# moduloComunicacao2-portas_l_gicas.net
KiCad netlist of a schematic drawn in EAGLE
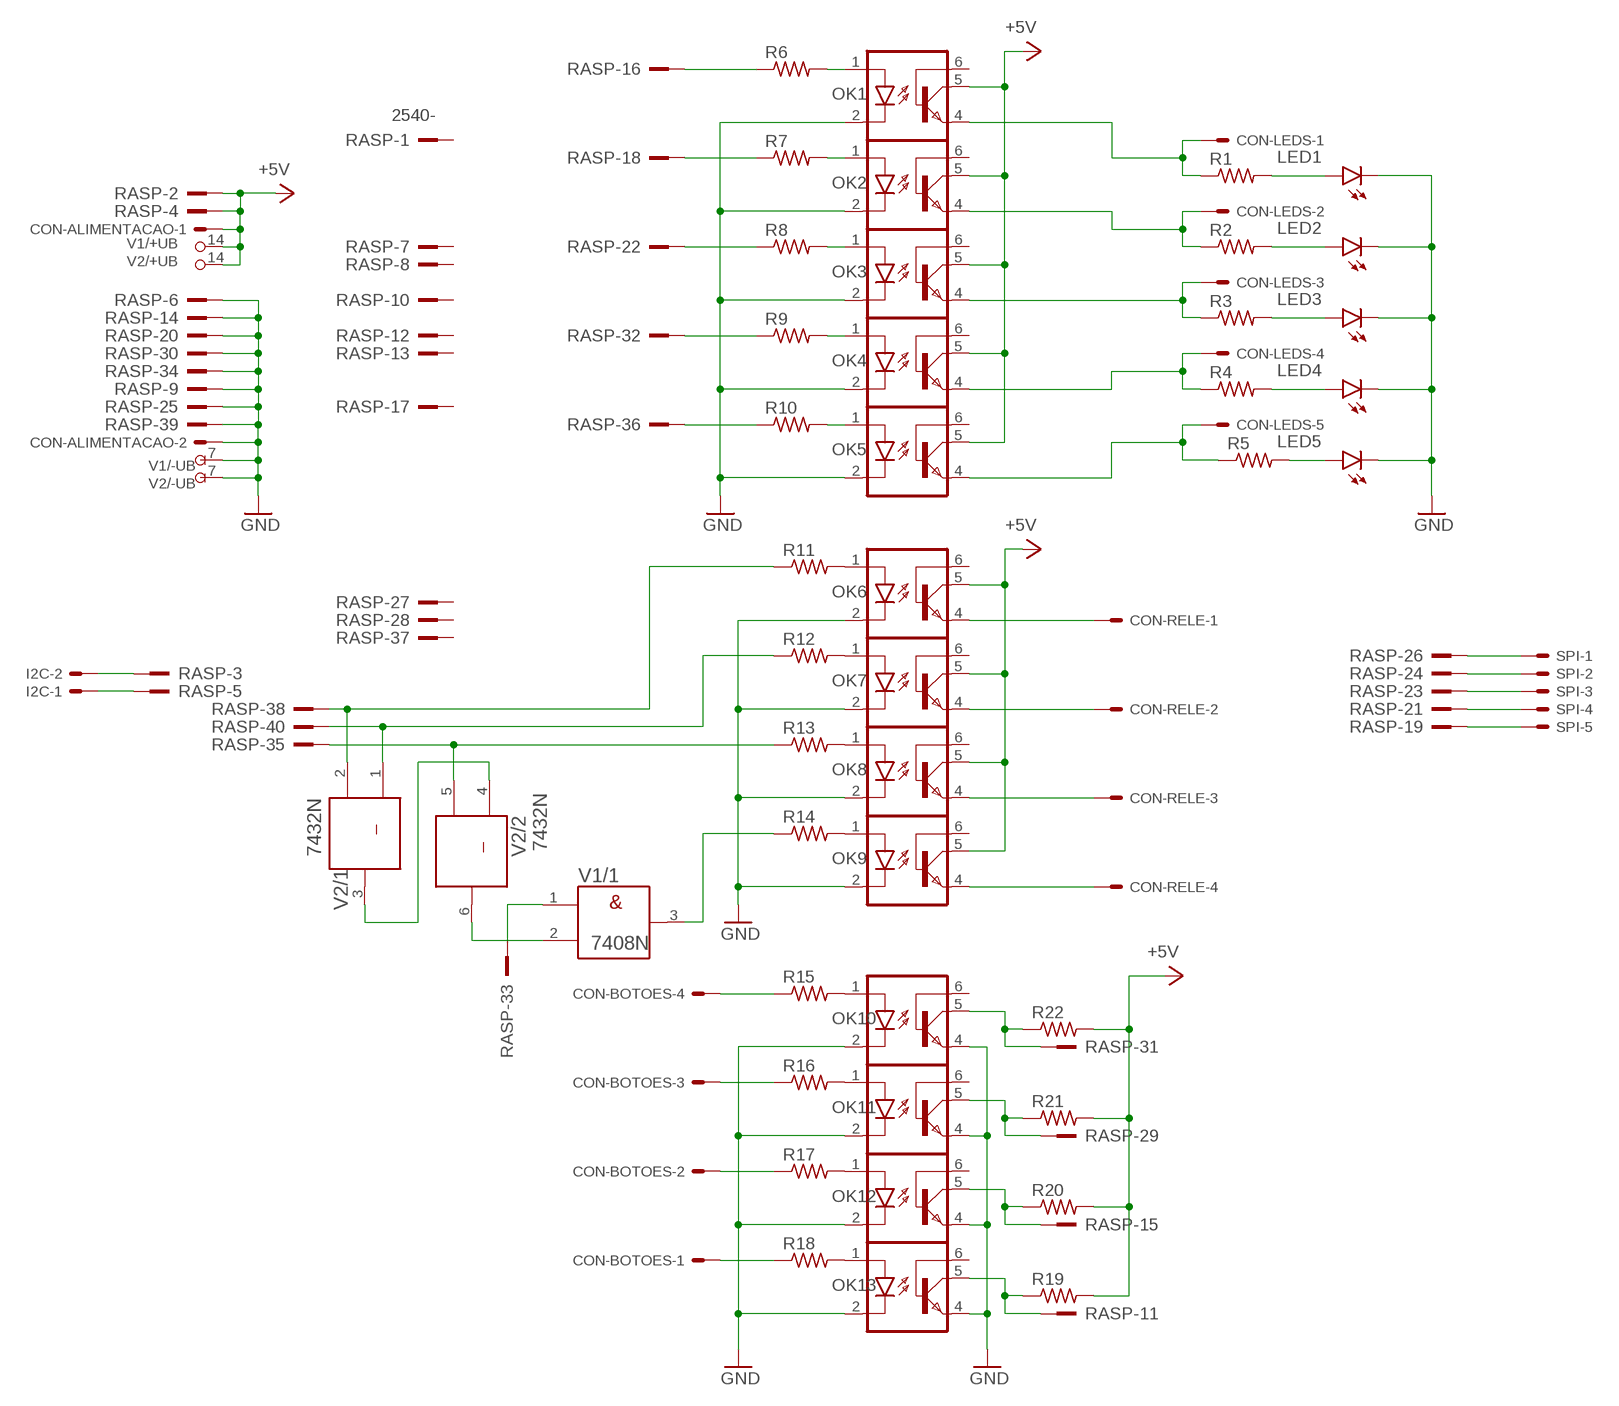
[diagram p0: schematic, sheet 1]

(export (version "E")
  (design (tool "Eeschema 10.0.6"))
  (components
    (comp (ref "CON-ALIMENTACAO")
      (value "22-23-2021")
      (footprint "eagle-import:22-23-2021")
      (fields (field (name "MF") "MOLEX"))
      (libsource (lib "eagle-import") (part "22-23-2021"))
    )
    (comp (ref "CON-BOTOES")
      (value "22-23-2041")
      (footprint "eagle-import:22-23-2041")
      (fields (field (name "MF") "MOLEX"))
      (libsource (lib "eagle-import") (part "22-23-2041"))
    )
    (comp (ref "CON-LEDS")
      (value "22-23-2051")
      (footprint "eagle-import:22-23-2051")
      (fields (field (name "MF") "MOLEX"))
      (libsource (lib "eagle-import") (part "22-23-2051"))
    )
    (comp (ref "CON-RELE")
      (value "22-23-2041")
      (footprint "eagle-import:22-23-2041")
      (fields (field (name "MF") "MOLEX"))
      (libsource (lib "eagle-import") (part "22-23-2041"))
    )
    (comp (ref "I2C")
      (value "22-23-2021")
      (footprint "eagle-import:22-23-2021")
      (fields (field (name "MF") "MOLEX"))
      (libsource (lib "eagle-import") (part "22-23-2021"))
    )
    (comp (ref "LED1")
      (value "LED5MM")
      (footprint "eagle-import:LED5MM")
      (libsource (lib "eagle-import") (part "LED5MM"))
    )
    (comp (ref "LED2")
      (value "LED5MM")
      (footprint "eagle-import:LED5MM")
      (libsource (lib "eagle-import") (part "LED5MM"))
    )
    (comp (ref "LED3")
      (value "LED5MM")
      (footprint "eagle-import:LED5MM")
      (libsource (lib "eagle-import") (part "LED5MM"))
    )
    (comp (ref "LED4")
      (value "LED5MM")
      (footprint "eagle-import:LED5MM")
      (libsource (lib "eagle-import") (part "LED5MM"))
    )
    (comp (ref "LED5")
      (value "LED5MM")
      (footprint "eagle-import:LED5MM")
      (libsource (lib "eagle-import") (part "LED5MM"))
    )
    (comp (ref "OK1")
      (value "4N25M")
      (footprint "eagle-import:DIL06")
      (fields (field (name "MPN") "4N25-M"))
      (libsource (lib "eagle-import") (part "4N?M25"))
    )
    (comp (ref "OK2")
      (value "4N25M")
      (footprint "eagle-import:DIL06")
      (fields (field (name "MPN") "4N25-M"))
      (libsource (lib "eagle-import") (part "4N?M25"))
    )
    (comp (ref "OK3")
      (value "4N25M")
      (footprint "eagle-import:DIL06")
      (fields (field (name "MPN") "4N25-M"))
      (libsource (lib "eagle-import") (part "4N?M25"))
    )
    (comp (ref "OK4")
      (value "4N25M")
      (footprint "eagle-import:DIL06")
      (fields (field (name "MPN") "4N25-M"))
      (libsource (lib "eagle-import") (part "4N?M25"))
    )
    (comp (ref "OK5")
      (value "4N25M")
      (footprint "eagle-import:DIL06")
      (fields (field (name "MPN") "4N25-M"))
      (libsource (lib "eagle-import") (part "4N?M25"))
    )
    (comp (ref "OK6")
      (value "4N25M")
      (footprint "eagle-import:DIL06")
      (fields (field (name "MPN") "4N25-M"))
      (libsource (lib "eagle-import") (part "4N?M25"))
    )
    (comp (ref "OK7")
      (value "4N25M")
      (footprint "eagle-import:DIL06")
      (fields (field (name "MPN") "4N25-M"))
      (libsource (lib "eagle-import") (part "4N?M25"))
    )
    (comp (ref "OK8")
      (value "4N25M")
      (footprint "eagle-import:DIL06")
      (fields (field (name "MPN") "4N25-M"))
      (libsource (lib "eagle-import") (part "4N?M25"))
    )
    (comp (ref "OK9")
      (value "4N25M")
      (footprint "eagle-import:DIL06")
      (fields (field (name "MPN") "4N25-M"))
      (libsource (lib "eagle-import") (part "4N?M25"))
    )
    (comp (ref "OK10")
      (value "4N25M")
      (footprint "eagle-import:DIL06")
      (fields (field (name "MPN") "4N25-M"))
      (libsource (lib "eagle-import") (part "4N?M25"))
    )
    (comp (ref "OK11")
      (value "4N25M")
      (footprint "eagle-import:DIL06")
      (fields (field (name "MPN") "4N25-M"))
      (libsource (lib "eagle-import") (part "4N?M25"))
    )
    (comp (ref "OK12")
      (value "4N25M")
      (footprint "eagle-import:DIL06")
      (fields (field (name "MPN") "4N25-M"))
      (libsource (lib "eagle-import") (part "4N?M25"))
    )
    (comp (ref "OK13")
      (value "4N25M")
      (footprint "eagle-import:DIL06")
      (fields (field (name "MPN") "4N25-M"))
      (libsource (lib "eagle-import") (part "4N?M25"))
    )
    (comp (ref "R1")
      (value "R-US_0207/12")
      (footprint "eagle-import:0207_12")
      (libsource (lib "eagle-import") (part "R-US_0207/12"))
    )
    (comp (ref "R2")
      (value "R-US_0207/12")
      (footprint "eagle-import:0207_12")
      (libsource (lib "eagle-import") (part "R-US_0207/12"))
    )
    (comp (ref "R3")
      (value "R-US_0207/12")
      (footprint "eagle-import:0207_12")
      (libsource (lib "eagle-import") (part "R-US_0207/12"))
    )
    (comp (ref "R4")
      (value "R-US_0207/12")
      (footprint "eagle-import:0207_12")
      (libsource (lib "eagle-import") (part "R-US_0207/12"))
    )
    (comp (ref "R5")
      (value "R-US_0207/12")
      (footprint "eagle-import:0207_12")
      (libsource (lib "eagle-import") (part "R-US_0207/12"))
    )
    (comp (ref "R6")
      (value "R-US_0204/7")
      (footprint "eagle-import:0204_7")
      (libsource (lib "eagle-import") (part "R-US_0204/7"))
    )
    (comp (ref "R7")
      (value "R-US_0204/7")
      (footprint "eagle-import:0204_7")
      (libsource (lib "eagle-import") (part "R-US_0204/7"))
    )
    (comp (ref "R8")
      (value "R-US_0204/7")
      (footprint "eagle-import:0204_7")
      (libsource (lib "eagle-import") (part "R-US_0204/7"))
    )
    (comp (ref "R9")
      (value "R-US_0204/7")
      (footprint "eagle-import:0204_7")
      (libsource (lib "eagle-import") (part "R-US_0204/7"))
    )
    (comp (ref "R10")
      (value "R-US_0204/7")
      (footprint "eagle-import:0204_7")
      (libsource (lib "eagle-import") (part "R-US_0204/7"))
    )
    (comp (ref "R11")
      (value "R-US_0204/7")
      (footprint "eagle-import:0204_7")
      (libsource (lib "eagle-import") (part "R-US_0204/7"))
    )
    (comp (ref "R12")
      (value "R-US_0204/7")
      (footprint "eagle-import:0204_7")
      (libsource (lib "eagle-import") (part "R-US_0204/7"))
    )
    (comp (ref "R13")
      (value "R-US_0204/7")
      (footprint "eagle-import:0204_7")
      (libsource (lib "eagle-import") (part "R-US_0204/7"))
    )
    (comp (ref "R14")
      (value "R-US_0204/7")
      (footprint "eagle-import:0204_7")
      (libsource (lib "eagle-import") (part "R-US_0204/7"))
    )
    (comp (ref "R15")
      (value "R-US_0207/10")
      (footprint "eagle-import:0207_10")
      (libsource (lib "eagle-import") (part "R-US_0207/10"))
    )
    (comp (ref "R16")
      (value "R-US_0207/10")
      (footprint "eagle-import:0207_10")
      (libsource (lib "eagle-import") (part "R-US_0207/10"))
    )
    (comp (ref "R17")
      (value "R-US_0207/10")
      (footprint "eagle-import:0207_10")
      (libsource (lib "eagle-import") (part "R-US_0207/10"))
    )
    (comp (ref "R18")
      (value "R-US_0207/10")
      (footprint "eagle-import:0207_10")
      (libsource (lib "eagle-import") (part "R-US_0207/10"))
    )
    (comp (ref "R19")
      (value "R-US_0204/7")
      (footprint "eagle-import:0204_7")
      (libsource (lib "eagle-import") (part "R-US_0204/7"))
    )
    (comp (ref "R20")
      (value "R-US_0204/7")
      (footprint "eagle-import:0204_7")
      (libsource (lib "eagle-import") (part "R-US_0204/7"))
    )
    (comp (ref "R21")
      (value "R-US_0204/7")
      (footprint "eagle-import:0204_7")
      (libsource (lib "eagle-import") (part "R-US_0204/7"))
    )
    (comp (ref "R22")
      (value "R-US_0204/7")
      (footprint "eagle-import:0204_7")
      (libsource (lib "eagle-import") (part "R-US_0204/7"))
    )
    (comp (ref "RASP")
      (value "2540-")
      (footprint "eagle-import:PAK100_2500-40")
      (libsource (lib "eagle-import") (part "2540-"))
    )
    (comp (ref "SPI")
      (value "22-23-2051")
      (footprint "eagle-import:22-23-2051")
      (fields (field (name "MF") "MOLEX"))
      (libsource (lib "eagle-import") (part "22-23-2051"))
    )
    (comp (ref "V1")
      (value "7408N")
      (footprint "eagle-import:DIL14")
      (libsource (lib "eagle-import") (part "7408N"))
    )
    (comp (ref "V2")
      (value "7432N")
      (footprint "eagle-import:DIL14")
      (libsource (lib "eagle-import") (part "7432N"))
    )
  )
  (nets
    (net (code "1") (name "+5V") (class "Default")
      (node (ref "CON-ALIMENTACAO") (pin "1") (pinfunction "S_1") (pintype "passive"))
      (node (ref "OK1") (pin "5") (pinfunction "COL_5") (pintype "passive"))
      (node (ref "OK2") (pin "5") (pinfunction "COL_5") (pintype "passive"))
      (node (ref "OK3") (pin "5") (pinfunction "COL_5") (pintype "passive"))
      (node (ref "OK4") (pin "5") (pinfunction "COL_5") (pintype "passive"))
      (node (ref "OK5") (pin "5") (pinfunction "COL_5") (pintype "passive"))
      (node (ref "OK6") (pin "5") (pinfunction "COL_5") (pintype "passive"))
      (node (ref "OK7") (pin "5") (pinfunction "COL_5") (pintype "passive"))
      (node (ref "OK8") (pin "5") (pinfunction "COL_5") (pintype "passive"))
      (node (ref "OK9") (pin "5") (pinfunction "COL_5") (pintype "passive"))
      (node (ref "R19") (pin "2") (pinfunction "2_2") (pintype "passive"))
      (node (ref "R20") (pin "2") (pinfunction "2_2") (pintype "passive"))
      (node (ref "R21") (pin "2") (pinfunction "2_2") (pintype "passive"))
      (node (ref "R22") (pin "2") (pinfunction "2_2") (pintype "passive"))
      (node (ref "RASP") (pin "2") (pinfunction "KL_2") (pintype "passive"))
      (node (ref "RASP") (pin "4") (pinfunction "KL_4") (pintype "passive"))
      (node (ref "V1") (pin "14") (pinfunction "+UB_14") (pintype "power_in"))
      (node (ref "V2") (pin "14") (pinfunction "+UB_14") (pintype "power_in"))
    )
    (net (code "2") (name "GND") (class "Default")
      (node (ref "CON-ALIMENTACAO") (pin "2") (pinfunction "S_2") (pintype "passive"))
      (node (ref "LED1") (pin "K") (pinfunction "C_K") (pintype "passive"))
      (node (ref "LED2") (pin "K") (pinfunction "C_K") (pintype "passive"))
      (node (ref "LED3") (pin "K") (pinfunction "C_K") (pintype "passive"))
      (node (ref "LED4") (pin "K") (pinfunction "C_K") (pintype "passive"))
      (node (ref "LED5") (pin "K") (pinfunction "C_K") (pintype "passive"))
      (node (ref "OK1") (pin "2") (pinfunction "C_2") (pintype "passive"))
      (node (ref "OK10") (pin "2") (pinfunction "C_2") (pintype "passive"))
      (node (ref "OK10") (pin "4") (pinfunction "EMI_4") (pintype "passive"))
      (node (ref "OK11") (pin "2") (pinfunction "C_2") (pintype "passive"))
      (node (ref "OK11") (pin "4") (pinfunction "EMI_4") (pintype "passive"))
      (node (ref "OK12") (pin "2") (pinfunction "C_2") (pintype "passive"))
      (node (ref "OK12") (pin "4") (pinfunction "EMI_4") (pintype "passive"))
      (node (ref "OK13") (pin "2") (pinfunction "C_2") (pintype "passive"))
      (node (ref "OK13") (pin "4") (pinfunction "EMI_4") (pintype "passive"))
      (node (ref "OK2") (pin "2") (pinfunction "C_2") (pintype "passive"))
      (node (ref "OK3") (pin "2") (pinfunction "C_2") (pintype "passive"))
      (node (ref "OK4") (pin "2") (pinfunction "C_2") (pintype "passive"))
      (node (ref "OK5") (pin "2") (pinfunction "C_2") (pintype "passive"))
      (node (ref "OK6") (pin "2") (pinfunction "C_2") (pintype "passive"))
      (node (ref "OK7") (pin "2") (pinfunction "C_2") (pintype "passive"))
      (node (ref "OK8") (pin "2") (pinfunction "C_2") (pintype "passive"))
      (node (ref "OK9") (pin "2") (pinfunction "C_2") (pintype "passive"))
      (node (ref "RASP") (pin "14") (pinfunction "KL_14") (pintype "passive"))
      (node (ref "RASP") (pin "20") (pinfunction "KL_20") (pintype "passive"))
      (node (ref "RASP") (pin "25") (pinfunction "KL_25") (pintype "passive"))
      (node (ref "RASP") (pin "30") (pinfunction "KL_30") (pintype "passive"))
      (node (ref "RASP") (pin "34") (pinfunction "KL_34") (pintype "passive"))
      (node (ref "RASP") (pin "39") (pinfunction "KL_39") (pintype "passive"))
      (node (ref "RASP") (pin "6") (pinfunction "KL_6") (pintype "passive"))
      (node (ref "RASP") (pin "9") (pinfunction "KL_9") (pintype "passive"))
      (node (ref "V1") (pin "7") (pinfunction "-UB_7") (pintype "power_in"))
      (node (ref "V2") (pin "7") (pinfunction "-UB_7") (pintype "power_in"))
    )
    (net (code "3") (name "Net-(CON-BOTOESA-S)") (class "Default")
      (node (ref "CON-BOTOES") (pin "1") (pinfunction "S_1") (pintype "passive"))
      (node (ref "R18") (pin "1") (pinfunction "1_1") (pintype "passive"))
    )
    (net (code "4") (name "Net-(CON-BOTOESB-S)") (class "Default")
      (node (ref "CON-BOTOES") (pin "2") (pinfunction "S_2") (pintype "passive"))
      (node (ref "R17") (pin "1") (pinfunction "1_1") (pintype "passive"))
    )
    (net (code "5") (name "Net-(CON-BOTOESC-S)") (class "Default")
      (node (ref "CON-BOTOES") (pin "3") (pinfunction "S_3") (pintype "passive"))
      (node (ref "R16") (pin "1") (pinfunction "1_1") (pintype "passive"))
    )
    (net (code "6") (name "Net-(CON-BOTOESD-S)") (class "Default")
      (node (ref "CON-BOTOES") (pin "4") (pinfunction "S_4") (pintype "passive"))
      (node (ref "R15") (pin "1") (pinfunction "1_1") (pintype "passive"))
    )
    (net (code "7") (name "Net-(CON-LEDSA-S)") (class "Default")
      (node (ref "CON-LEDS") (pin "1") (pinfunction "S_1") (pintype "passive"))
      (node (ref "OK1") (pin "4") (pinfunction "EMI_4") (pintype "passive"))
      (node (ref "R1") (pin "1") (pinfunction "1_1") (pintype "passive"))
    )
    (net (code "8") (name "Net-(CON-LEDSB-S)") (class "Default")
      (node (ref "CON-LEDS") (pin "2") (pinfunction "S_2") (pintype "passive"))
      (node (ref "OK2") (pin "4") (pinfunction "EMI_4") (pintype "passive"))
      (node (ref "R2") (pin "1") (pinfunction "1_1") (pintype "passive"))
    )
    (net (code "9") (name "Net-(CON-LEDSC-S)") (class "Default")
      (node (ref "CON-LEDS") (pin "3") (pinfunction "S_3") (pintype "passive"))
      (node (ref "OK3") (pin "4") (pinfunction "EMI_4") (pintype "passive"))
      (node (ref "R3") (pin "1") (pinfunction "1_1") (pintype "passive"))
    )
    (net (code "10") (name "Net-(CON-LEDSD-S)") (class "Default")
      (node (ref "CON-LEDS") (pin "4") (pinfunction "S_4") (pintype "passive"))
      (node (ref "OK4") (pin "4") (pinfunction "EMI_4") (pintype "passive"))
      (node (ref "R4") (pin "1") (pinfunction "1_1") (pintype "passive"))
    )
    (net (code "11") (name "Net-(CON-LEDSE-S)") (class "Default")
      (node (ref "CON-LEDS") (pin "5") (pinfunction "S_5") (pintype "passive"))
      (node (ref "OK5") (pin "4") (pinfunction "EMI_4") (pintype "passive"))
      (node (ref "R5") (pin "1") (pinfunction "1_1") (pintype "passive"))
    )
    (net (code "12") (name "Net-(CON-RELEA-S)") (class "Default")
      (node (ref "CON-RELE") (pin "1") (pinfunction "S_1") (pintype "passive"))
      (node (ref "OK6") (pin "4") (pinfunction "EMI_4") (pintype "passive"))
    )
    (net (code "13") (name "Net-(CON-RELEB-S)") (class "Default")
      (node (ref "CON-RELE") (pin "2") (pinfunction "S_2") (pintype "passive"))
      (node (ref "OK7") (pin "4") (pinfunction "EMI_4") (pintype "passive"))
    )
    (net (code "14") (name "Net-(CON-RELEC-S)") (class "Default")
      (node (ref "CON-RELE") (pin "3") (pinfunction "S_3") (pintype "passive"))
      (node (ref "OK8") (pin "4") (pinfunction "EMI_4") (pintype "passive"))
    )
    (net (code "15") (name "Net-(CON-RELED-S)") (class "Default")
      (node (ref "CON-RELE") (pin "4") (pinfunction "S_4") (pintype "passive"))
      (node (ref "OK9") (pin "4") (pinfunction "EMI_4") (pintype "passive"))
    )
    (net (code "16") (name "Net-(I2CA-S)") (class "Default")
      (node (ref "I2C") (pin "1") (pinfunction "S_1") (pintype "passive"))
      (node (ref "RASP") (pin "5") (pinfunction "KL_5") (pintype "passive"))
    )
    (net (code "17") (name "Net-(I2CB-S)") (class "Default")
      (node (ref "I2C") (pin "2") (pinfunction "S_2") (pintype "passive"))
      (node (ref "RASP") (pin "3") (pinfunction "KL_3") (pintype "passive"))
    )
    (net (code "18") (name "Net-(LED1-PadA)") (class "Default")
      (node (ref "LED1") (pin "A") (pinfunction "A_A") (pintype "passive"))
      (node (ref "R1") (pin "2") (pinfunction "2_2") (pintype "passive"))
    )
    (net (code "19") (name "Net-(LED2-PadA)") (class "Default")
      (node (ref "LED2") (pin "A") (pinfunction "A_A") (pintype "passive"))
      (node (ref "R2") (pin "2") (pinfunction "2_2") (pintype "passive"))
    )
    (net (code "20") (name "Net-(LED3-PadA)") (class "Default")
      (node (ref "LED3") (pin "A") (pinfunction "A_A") (pintype "passive"))
      (node (ref "R3") (pin "2") (pinfunction "2_2") (pintype "passive"))
    )
    (net (code "21") (name "Net-(LED4-PadA)") (class "Default")
      (node (ref "LED4") (pin "A") (pinfunction "A_A") (pintype "passive"))
      (node (ref "R4") (pin "2") (pinfunction "2_2") (pintype "passive"))
    )
    (net (code "22") (name "Net-(LED5-PadA)") (class "Default")
      (node (ref "LED5") (pin "A") (pinfunction "A_A") (pintype "passive"))
      (node (ref "R5") (pin "2") (pinfunction "2_2") (pintype "passive"))
    )
    (net (code "23") (name "Net-(OK1-A)") (class "Default")
      (node (ref "OK1") (pin "1") (pinfunction "A_1") (pintype "passive"))
      (node (ref "R6") (pin "2") (pinfunction "2_2") (pintype "passive"))
    )
    (net (code "24") (name "Net-(OK2-A)") (class "Default")
      (node (ref "OK2") (pin "1") (pinfunction "A_1") (pintype "passive"))
      (node (ref "R7") (pin "2") (pinfunction "2_2") (pintype "passive"))
    )
    (net (code "25") (name "Net-(OK3-A)") (class "Default")
      (node (ref "OK3") (pin "1") (pinfunction "A_1") (pintype "passive"))
      (node (ref "R8") (pin "2") (pinfunction "2_2") (pintype "passive"))
    )
    (net (code "26") (name "Net-(OK4-A)") (class "Default")
      (node (ref "OK4") (pin "1") (pinfunction "A_1") (pintype "passive"))
      (node (ref "R9") (pin "2") (pinfunction "2_2") (pintype "passive"))
    )
    (net (code "27") (name "Net-(OK5-A)") (class "Default")
      (node (ref "OK5") (pin "1") (pinfunction "A_1") (pintype "passive"))
      (node (ref "R10") (pin "2") (pinfunction "2_2") (pintype "passive"))
    )
    (net (code "28") (name "Net-(OK6-A)") (class "Default")
      (node (ref "OK6") (pin "1") (pinfunction "A_1") (pintype "passive"))
      (node (ref "R11") (pin "2") (pinfunction "2_2") (pintype "passive"))
    )
    (net (code "29") (name "Net-(OK7-A)") (class "Default")
      (node (ref "OK7") (pin "1") (pinfunction "A_1") (pintype "passive"))
      (node (ref "R12") (pin "2") (pinfunction "2_2") (pintype "passive"))
    )
    (net (code "30") (name "Net-(OK8-A)") (class "Default")
      (node (ref "OK8") (pin "1") (pinfunction "A_1") (pintype "passive"))
      (node (ref "R13") (pin "2") (pinfunction "2_2") (pintype "passive"))
    )
    (net (code "31") (name "Net-(OK9-A)") (class "Default")
      (node (ref "OK9") (pin "1") (pinfunction "A_1") (pintype "passive"))
      (node (ref "R14") (pin "2") (pinfunction "2_2") (pintype "passive"))
    )
    (net (code "32") (name "Net-(OK10-A)") (class "Default")
      (node (ref "OK10") (pin "1") (pinfunction "A_1") (pintype "passive"))
      (node (ref "R15") (pin "2") (pinfunction "2_2") (pintype "passive"))
    )
    (net (code "33") (name "Net-(OK10-COL)") (class "Default")
      (node (ref "OK10") (pin "5") (pinfunction "COL_5") (pintype "passive"))
      (node (ref "R22") (pin "1") (pinfunction "1_1") (pintype "passive"))
      (node (ref "RASP") (pin "31") (pinfunction "KL_31") (pintype "passive"))
    )
    (net (code "34") (name "Net-(OK11-A)") (class "Default")
      (node (ref "OK11") (pin "1") (pinfunction "A_1") (pintype "passive"))
      (node (ref "R16") (pin "2") (pinfunction "2_2") (pintype "passive"))
    )
    (net (code "35") (name "Net-(OK11-COL)") (class "Default")
      (node (ref "OK11") (pin "5") (pinfunction "COL_5") (pintype "passive"))
      (node (ref "R21") (pin "1") (pinfunction "1_1") (pintype "passive"))
      (node (ref "RASP") (pin "29") (pinfunction "KL_29") (pintype "passive"))
    )
    (net (code "36") (name "Net-(OK12-A)") (class "Default")
      (node (ref "OK12") (pin "1") (pinfunction "A_1") (pintype "passive"))
      (node (ref "R17") (pin "2") (pinfunction "2_2") (pintype "passive"))
    )
    (net (code "37") (name "Net-(OK12-COL)") (class "Default")
      (node (ref "OK12") (pin "5") (pinfunction "COL_5") (pintype "passive"))
      (node (ref "R20") (pin "1") (pinfunction "1_1") (pintype "passive"))
      (node (ref "RASP") (pin "15") (pinfunction "KL_15") (pintype "passive"))
    )
    (net (code "38") (name "Net-(OK13-A)") (class "Default")
      (node (ref "OK13") (pin "1") (pinfunction "A_1") (pintype "passive"))
      (node (ref "R18") (pin "2") (pinfunction "2_2") (pintype "passive"))
    )
    (net (code "39") (name "Net-(OK13-COL)") (class "Default")
      (node (ref "OK13") (pin "5") (pinfunction "COL_5") (pintype "passive"))
      (node (ref "R19") (pin "1") (pinfunction "1_1") (pintype "passive"))
      (node (ref "RASP") (pin "11") (pinfunction "KL_11") (pintype "passive"))
    )
    (net (code "40") (name "Net-(RASPAA-KL)") (class "Default")
      (node (ref "RASP") (pin "33") (pinfunction "KL_33") (pintype "passive"))
      (node (ref "V1") (pin "1") (pinfunction "A_1") (pintype "input"))
    )
    (net (code "41") (name "Net-(RASPAC-KL)") (class "Default")
      (node (ref "R13") (pin "1") (pinfunction "1_1") (pintype "passive"))
      (node (ref "RASP") (pin "35") (pinfunction "KL_35") (pintype "passive"))
      (node (ref "V2") (pin "5") (pinfunction "B_5") (pintype "input"))
    )
    (net (code "42") (name "Net-(RASPAD-KL)") (class "Default")
      (node (ref "R10") (pin "1") (pinfunction "1_1") (pintype "passive"))
      (node (ref "RASP") (pin "36") (pinfunction "KL_36") (pintype "passive"))
    )
    (net (code "43") (name "Net-(RASPAF-KL)") (class "Default")
      (node (ref "R11") (pin "1") (pinfunction "1_1") (pintype "passive"))
      (node (ref "RASP") (pin "38") (pinfunction "KL_38") (pintype "passive"))
      (node (ref "V2") (pin "2") (pinfunction "B_2") (pintype "input"))
    )
    (net (code "44") (name "Net-(RASPAI-KL)") (class "Default")
      (node (ref "R12") (pin "1") (pinfunction "1_1") (pintype "passive"))
      (node (ref "RASP") (pin "40") (pinfunction "KL_40") (pintype "passive"))
      (node (ref "V2") (pin "1") (pinfunction "A_1") (pintype "input"))
    )
    (net (code "45") (name "Net-(RASPH-KL)") (class "Default")
      (node (ref "R6") (pin "1") (pinfunction "1_1") (pintype "passive"))
      (node (ref "RASP") (pin "16") (pinfunction "KL_16") (pintype "passive"))
    )
    (net (code "46") (name "Net-(RASPJ-KL)") (class "Default")
      (node (ref "R7") (pin "1") (pinfunction "1_1") (pintype "passive"))
      (node (ref "RASP") (pin "18") (pinfunction "KL_18") (pintype "passive"))
    )
    (net (code "47") (name "Net-(RASPK-KL)") (class "Default")
      (node (ref "RASP") (pin "19") (pinfunction "KL_19") (pintype "passive"))
      (node (ref "SPI") (pin "5") (pinfunction "S_5") (pintype "passive"))
    )
    (net (code "48") (name "Net-(RASPN-KL)") (class "Default")
      (node (ref "RASP") (pin "21") (pinfunction "KL_21") (pintype "passive"))
      (node (ref "SPI") (pin "4") (pinfunction "S_4") (pintype "passive"))
    )
    (net (code "49") (name "Net-(RASPO-KL)") (class "Default")
      (node (ref "R8") (pin "1") (pinfunction "1_1") (pintype "passive"))
      (node (ref "RASP") (pin "22") (pinfunction "KL_22") (pintype "passive"))
    )
    (net (code "50") (name "Net-(RASPP-KL)") (class "Default")
      (node (ref "RASP") (pin "23") (pinfunction "KL_23") (pintype "passive"))
      (node (ref "SPI") (pin "3") (pinfunction "S_3") (pintype "passive"))
    )
    (net (code "51") (name "Net-(RASPQ-KL)") (class "Default")
      (node (ref "RASP") (pin "24") (pinfunction "KL_24") (pintype "passive"))
      (node (ref "SPI") (pin "2") (pinfunction "S_2") (pintype "passive"))
    )
    (net (code "52") (name "Net-(RASPS-KL)") (class "Default")
      (node (ref "RASP") (pin "26") (pinfunction "KL_26") (pintype "passive"))
      (node (ref "SPI") (pin "1") (pinfunction "S_1") (pintype "passive"))
    )
    (net (code "53") (name "Net-(RASPZ-KL)") (class "Default")
      (node (ref "R9") (pin "1") (pinfunction "1_1") (pintype "passive"))
      (node (ref "RASP") (pin "32") (pinfunction "KL_32") (pintype "passive"))
    )
    (net (code "54") (name "Net-(V1C-B)") (class "Default")
      (node (ref "V1") (pin "2") (pinfunction "B_2") (pintype "input"))
      (node (ref "V2") (pin "6") (pinfunction "Y_6") (pintype "output"))
    )
    (net (code "55") (name "Net-(V1C-Y)") (class "Default")
      (node (ref "R14") (pin "1") (pinfunction "1_1") (pintype "passive"))
      (node (ref "V1") (pin "3") (pinfunction "Y_3") (pintype "output"))
    )
    (net (code "56") (name "Net-(V2C-Y)") (class "Default")
      (node (ref "V2") (pin "3") (pinfunction "Y_3") (pintype "output"))
      (node (ref "V2") (pin "4") (pinfunction "A_4") (pintype "input"))
    )
    (net (code "57") (name "unconnected-(OK1-BAS-Pad6)") (class "Default")
      (node (ref "OK1") (pin "6") (pinfunction "BAS_6") (pintype "passive"))
    )
    (net (code "58") (name "unconnected-(OK2-BAS-Pad6)") (class "Default")
      (node (ref "OK2") (pin "6") (pinfunction "BAS_6") (pintype "passive"))
    )
    (net (code "59") (name "unconnected-(OK3-BAS-Pad6)") (class "Default")
      (node (ref "OK3") (pin "6") (pinfunction "BAS_6") (pintype "passive"))
    )
    (net (code "60") (name "unconnected-(OK4-BAS-Pad6)") (class "Default")
      (node (ref "OK4") (pin "6") (pinfunction "BAS_6") (pintype "passive"))
    )
    (net (code "61") (name "unconnected-(OK5-BAS-Pad6)") (class "Default")
      (node (ref "OK5") (pin "6") (pinfunction "BAS_6") (pintype "passive"))
    )
    (net (code "62") (name "unconnected-(OK6-BAS-Pad6)") (class "Default")
      (node (ref "OK6") (pin "6") (pinfunction "BAS_6") (pintype "passive"))
    )
    (net (code "63") (name "unconnected-(OK7-BAS-Pad6)") (class "Default")
      (node (ref "OK7") (pin "6") (pinfunction "BAS_6") (pintype "passive"))
    )
    (net (code "64") (name "unconnected-(OK8-BAS-Pad6)") (class "Default")
      (node (ref "OK8") (pin "6") (pinfunction "BAS_6") (pintype "passive"))
    )
    (net (code "65") (name "unconnected-(OK9-BAS-Pad6)") (class "Default")
      (node (ref "OK9") (pin "6") (pinfunction "BAS_6") (pintype "passive"))
    )
    (net (code "66") (name "unconnected-(OK10-BAS-Pad6)") (class "Default")
      (node (ref "OK10") (pin "6") (pinfunction "BAS_6") (pintype "passive"))
    )
    (net (code "67") (name "unconnected-(OK11-BAS-Pad6)") (class "Default")
      (node (ref "OK11") (pin "6") (pinfunction "BAS_6") (pintype "passive"))
    )
    (net (code "68") (name "unconnected-(OK12-BAS-Pad6)") (class "Default")
      (node (ref "OK12") (pin "6") (pinfunction "BAS_6") (pintype "passive"))
    )
    (net (code "69") (name "unconnected-(OK13-BAS-Pad6)") (class "Default")
      (node (ref "OK13") (pin "6") (pinfunction "BAS_6") (pintype "passive"))
    )
    (net (code "70") (name "unconnected-(RASPA-KL-Pad1)") (class "Default")
      (node (ref "RASP") (pin "1") (pinfunction "KL_1") (pintype "passive"))
    )
    (net (code "71") (name "unconnected-(RASPAE-KL-Pad37)") (class "Default")
      (node (ref "RASP") (pin "37") (pinfunction "KL_37") (pintype "passive"))
    )
    (net (code "72") (name "unconnected-(RASPAL-KL-Pad7)") (class "Default")
      (node (ref "RASP") (pin "7") (pinfunction "KL_7") (pintype "passive"))
    )
    (net (code "73") (name "unconnected-(RASPAM-KL-Pad8)") (class "Default")
      (node (ref "RASP") (pin "8") (pinfunction "KL_8") (pintype "passive"))
    )
    (net (code "74") (name "unconnected-(RASPB-KL-Pad10)") (class "Default")
      (node (ref "RASP") (pin "10") (pinfunction "KL_10") (pintype "passive"))
    )
    (net (code "75") (name "unconnected-(RASPD-KL-Pad12)") (class "Default")
      (node (ref "RASP") (pin "12") (pinfunction "KL_12") (pintype "passive"))
    )
    (net (code "76") (name "unconnected-(RASPE-KL-Pad13)") (class "Default")
      (node (ref "RASP") (pin "13") (pinfunction "KL_13") (pintype "passive"))
    )
    (net (code "77") (name "unconnected-(RASPI-KL-Pad17)") (class "Default")
      (node (ref "RASP") (pin "17") (pinfunction "KL_17") (pintype "passive"))
    )
    (net (code "78") (name "unconnected-(RASPT-KL-Pad27)") (class "Default")
      (node (ref "RASP") (pin "27") (pinfunction "KL_27") (pintype "passive"))
    )
    (net (code "79") (name "unconnected-(RASPU-KL-Pad28)") (class "Default")
      (node (ref "RASP") (pin "28") (pinfunction "KL_28") (pintype "passive"))
    )
  )
)
